# 4__SIM.net
KiCad netlist of a schematic drawn in Altium Designer
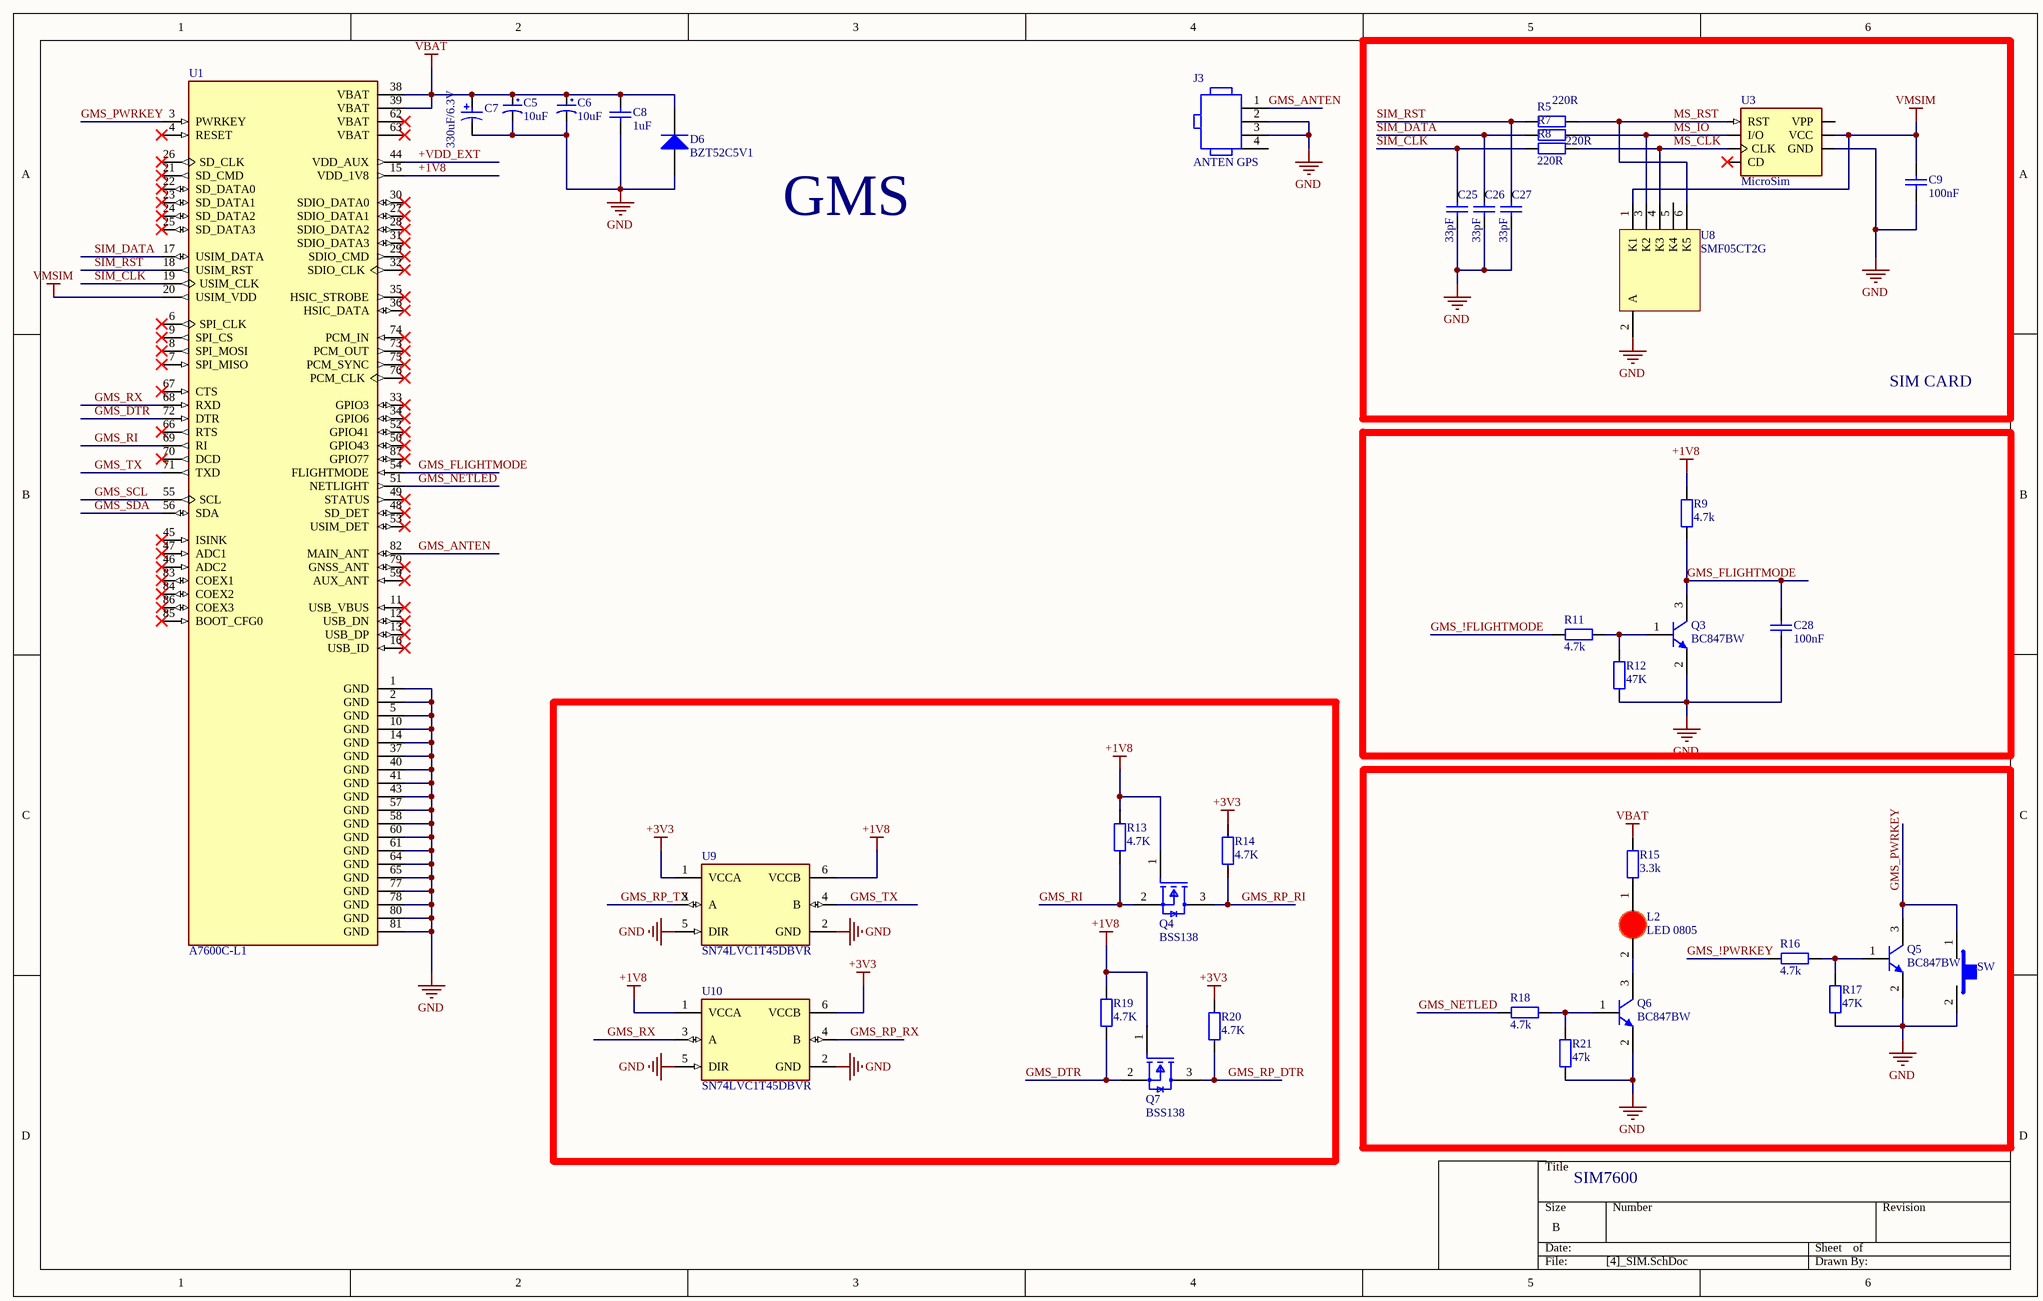
[diagram p0: [4]_SIM.SchDoc]

(export (version "E")
  (design (tool "Eeschema 10.0.6"))
  (components
    (comp (ref "C5")
      (value "10uF")
      (footprint "tu tantalum smd3528")
      (description "Dán")
      (libsource (lib "Altium_Lib_by_KhueNguyenCreator") (part "Tu tantalum 10uF 16V SMD3528"))
    )
    (comp (ref "C6")
      (value "10uF")
      (footprint "tu tantalum smd3528")
      (description "Dán")
      (libsource (lib "Altium_Lib_by_KhueNguyenCreator") (part "Tu tantalum 10uF 16V SMD3528"))
    )
    (comp (ref "C7")
      (value "330uF/6.3V")
      (footprint "NIC-CAPA2-6.3X7.7_V")
      (fields (field (name "PARTNUMBER") "UUD0J331MCL1GS") (field (name "MANUFACTURER") "Nichicon"))
      (libsource (lib "Altium Content Vault") (part "NIC-CAP-P-2"))
    )
    (comp (ref "C8")
      (value "1uF")
      (footprint "tu 0603")
      (description "Dán")
      (libsource (lib "Altium_Lib_by_KhueNguyenCreator") (part "Tu 0603 104 50V 10%"))
    )
    (comp (ref "C9")
      (value "100nF")
      (footprint "tu 0603")
      (description "Dán")
      (libsource (lib "Altium_Lib_by_KhueNguyenCreator") (part "Tu 0603 105 16V 20%"))
    )
    (comp (ref "C25")
      (value "33pF")
      (footprint "tu 0603")
      (description "Dán")
      (libsource (lib "Altium_Lib_by_KhueNguyenCreator") (part "Tu 0603 104 50V 10%"))
    )
    (comp (ref "C26")
      (value "33pF")
      (footprint "tu 0603")
      (description "Dán")
      (libsource (lib "Altium_Lib_by_KhueNguyenCreator") (part "Tu 0603 104 50V 10%"))
    )
    (comp (ref "C27")
      (value "33pF")
      (footprint "tu 0603")
      (description "Dán")
      (libsource (lib "Altium_Lib_by_KhueNguyenCreator") (part "Tu 0603 104 50V 10%"))
    )
    (comp (ref "C28")
      (value "100nF")
      (footprint "tu 0603")
      (description "Dán")
      (libsource (lib "Altium_Lib_by_KhueNguyenCreator") (part "Tu 0603 105 16V 20%"))
    )
    (comp (ref "D6")
      (value "BZT52C5V1")
      (footprint "DIODE SOD-123")
      (description "Dán")
      (libsource (lib "Altium_Lib_by_KhueNguyenCreator") (part "Diode S4"))
    )
    (comp (ref "J3")
      (value "ANTEN GPS")
      (footprint "TG-RECE-20369-001E-4_V")
      (description "RF Connector, Onboard Receptacle, IPEX MHFIII")
      (fields (field (name "MANUFACTURER") "Taoglas") (field (name "PARTNUMBER") "RECE-20369-001E-01"))
      (libsource (lib "Altium Content Vault") (part "TG-RECE-20369-001E-01-4"))
    )
    (comp (ref "L2")
      (value "LED 0805")
      (footprint "LED-0805-Red")
      (description "Dán")
      (libsource (lib "Altium_Lib_by_KhueNguyenCreator") (part "LED 0805 Do"))
    )
    (comp (ref "Q3")
      (value "BC847BW")
      (footprint "INF-SOT323_N")
      (description "NPN Silicon AF Transistor, 45 V VCEO, 100 mA IC, SOT323, Reel, Green")
      (fields (field (name "MANUFACTURER") "Infineon"))
      (libsource (lib "Altium Content Vault") (part "INF-BJTNPN-BEC-3"))
    )
    (comp (ref "Q4")
      (value "BSS138")
      (footprint "FP-SOT23-IPC_C")
      (description "MOSFET N-CH 50V 500MA SOT23")
      (libsource (lib "Altium Content Vault") (part "0a9ea7c96deaaede766a5b531c28de0"))
    )
    (comp (ref "Q5")
      (value "BC847BW")
      (footprint "INF-SOT323_N")
      (description "NPN Silicon AF Transistor, 45 V VCEO, 100 mA IC, SOT323, Reel, Green")
      (fields (field (name "MANUFACTURER") "Infineon"))
      (libsource (lib "Altium Content Vault") (part "INF-BJTNPN-BEC-3"))
    )
    (comp (ref "Q6")
      (value "BC847BW")
      (footprint "INF-SOT323_N")
      (description "NPN Silicon AF Transistor, 45 V VCEO, 100 mA IC, SOT323, Reel, Green")
      (fields (field (name "MANUFACTURER") "Infineon"))
      (libsource (lib "Altium Content Vault") (part "INF-BJTNPN-BEC-3"))
    )
    (comp (ref "Q7")
      (value "BSS138")
      (footprint "FP-SOT23-IPC_C")
      (description "MOSFET N-CH 50V 500MA SOT23")
      (libsource (lib "Altium Content Vault") (part "0a9ea7c96deaaede766a5b531c28de0"))
    )
    (comp (ref "R5")
      (value "220R")
      (footprint "tro smd 0603")
      (description "Dán")
      (libsource (lib "Altium_Lib_by_KhueNguyenCreator") (part "Tro 0603 5% 220R"))
    )
    (comp (ref "R7")
      (value "220R")
      (footprint "tro smd 0603")
      (description "Dán")
      (libsource (lib "Altium_Lib_by_KhueNguyenCreator") (part "Tro 0603 5% 220R"))
    )
    (comp (ref "R8")
      (value "220R")
      (footprint "tro smd 0603")
      (description "Dán")
      (libsource (lib "Altium_Lib_by_KhueNguyenCreator") (part "Tro 0603 5% 220R"))
    )
    (comp (ref "R9")
      (value "4.7k")
      (footprint "tro smd 0603")
      (description "Dán")
      (libsource (lib "Altium_Lib_by_KhueNguyenCreator") (part "Tro 0603 5% 1k"))
    )
    (comp (ref "R11")
      (value "4.7k")
      (footprint "tro smd 0603")
      (description "Dán")
      (libsource (lib "Altium_Lib_by_KhueNguyenCreator") (part "Tro 0603 5% 1k"))
    )
    (comp (ref "R12")
      (value "47K")
      (footprint "tro smd 0603")
      (description "Dán")
      (libsource (lib "Altium_Lib_by_KhueNguyenCreator") (part "Tro 0603 5% 100k"))
    )
    (comp (ref "R13")
      (value "4.7K")
      (footprint "tro smd 0603")
      (description "Dán")
      (libsource (lib "Altium_Lib_by_KhueNguyenCreator") (part "Tro 0603 5% 1k"))
    )
    (comp (ref "R14")
      (value "4.7K")
      (footprint "tro smd 0603")
      (description "Dán")
      (libsource (lib "Altium_Lib_by_KhueNguyenCreator") (part "Tro 0603 5% 1k"))
    )
    (comp (ref "R15")
      (value "3.3k")
      (footprint "tro smd 0603")
      (description "Dán")
      (libsource (lib "Altium_Lib_by_KhueNguyenCreator") (part "Tro 0603 5% 1k"))
    )
    (comp (ref "R16")
      (value "4.7k")
      (footprint "tro smd 0603")
      (description "Dán")
      (libsource (lib "Altium_Lib_by_KhueNguyenCreator") (part "Tro 0603 5% 1k"))
    )
    (comp (ref "R17")
      (value "47K")
      (footprint "tro smd 0603")
      (description "Dán")
      (libsource (lib "Altium_Lib_by_KhueNguyenCreator") (part "Tro 0603 5% 100k"))
    )
    (comp (ref "R18")
      (value "4.7k")
      (footprint "tro smd 0603")
      (description "Dán")
      (libsource (lib "Altium_Lib_by_KhueNguyenCreator") (part "Tro 0603 5% 1k"))
    )
    (comp (ref "R19")
      (value "4.7K")
      (footprint "tro smd 0603")
      (description "Dán")
      (libsource (lib "Altium_Lib_by_KhueNguyenCreator") (part "Tro 0603 5% 1k"))
    )
    (comp (ref "R20")
      (value "4.7K")
      (footprint "tro smd 0603")
      (description "Dán")
      (libsource (lib "Altium_Lib_by_KhueNguyenCreator") (part "Tro 0603 5% 1k"))
    )
    (comp (ref "R21")
      (value "47k")
      (footprint "tro smd 0603")
      (description "Dán")
      (libsource (lib "Altium_Lib_by_KhueNguyenCreator") (part "Tro 0603 5% 100k"))
    )
    (comp (ref "SW")
      (value "Tactile")
      (footprint "SW 2P SMD")
      (description "SMD Mini Push Button Switch 2 Pin 3x6x2.7mm")
      (fields (field (name "MANUFACTURER") "OEM") (field (name "PART NUMBER") "SPST 2 PIN SMD"))
      (libsource (lib "COMPONENT_INS") (part "SW_SPDT_2PIN"))
    )
    (comp (ref "U1")
      (value "A7600C-L1")
      (footprint "SIMA7600C")
      (libsource (lib "COMPONENT_INS") (part "SIMA7600C"))
    )
    (comp (ref "U3")
      (value "MicroSim")
      (footprint "Micro-Sim-7P")
      (description "MS-PP-7P Khay Cắm Micro Sim 7 Chân Push-Push")
      (fields (field (name "MANUFACTURER") "Samsung") (field (name "PART NUMBER") "C0805"))
      (libsource (lib "COMPONENT_INS") (part "Micro_Sim_7Pin"))
    )
    (comp (ref "U8")
      (value "SMF05CT2G")
      (footprint "ONSC-SC70-6-419B-02_W_V")
      (description "5-Line Transient Voltage Suppressor Array, 6-Pin SC70, Pb-Free, Tape and Reel")
      (fields (field (name "MANUFACTURER") "On Semiconductor"))
      (libsource (lib "Altium Content Vault") (part "ONSC-K1A2K3K4K5K6-6"))
    )
    (comp (ref "U9")
      (value "SN74LVC1T45DBVR")
      (footprint "FP-DBV0006A-IPC_B")
      (description "IC TRNSLTR BIDIRECTIONAL SOT23-6")
      (libsource (lib "Altium Content Vault") (part "7317ea058f373ab919a7c78c581a60e"))
    )
    (comp (ref "U10")
      (value "SN74LVC1T45DBVR")
      (footprint "FP-DBV0006A-IPC_B")
      (description "IC TRNSLTR BIDIRECTIONAL SOT23-6")
      (libsource (lib "Altium Content Vault") (part "7317ea058f373ab919a7c78c581a60e"))
    )
  )
  (nets
    (net (code "1") (name "+1V8") (class "Default")
      (node (ref "Q4") (pin "1") (pinfunction "G_1") (pintype "passive"))
      (node (ref "Q7") (pin "1") (pinfunction "G_1") (pintype "passive"))
      (node (ref "R13") (pin "1") (pinfunction "1_1") (pintype "passive"))
      (node (ref "R19") (pin "1") (pinfunction "1_1") (pintype "passive"))
      (node (ref "R9") (pin "2") (pinfunction "2_2") (pintype "passive"))
      (node (ref "U1") (pin "15") (pinfunction "VDD_1V8_15") (pintype "output"))
      (node (ref "U10") (pin "1") (pinfunction "VCCA_1") (pintype "power_in"))
      (node (ref "U9") (pin "6") (pinfunction "VCCB_6") (pintype "power_in"))
    )
    (net (code "2") (name "+3V3") (class "Default")
      (node (ref "R14") (pin "2") (pinfunction "2_2") (pintype "passive"))
      (node (ref "R20") (pin "2") (pinfunction "2_2") (pintype "passive"))
      (node (ref "U10") (pin "6") (pinfunction "VCCB_6") (pintype "power_in"))
      (node (ref "U9") (pin "1") (pinfunction "VCCA_1") (pintype "power_in"))
    )
    (net (code "3") (name "/+VDD_EXT") (class "Default")
      (node (ref "U1") (pin "44") (pinfunction "VDD_AUX_44") (pintype "output"))
    )
    (net (code "5") (name "/GMS_!FLIGHTMODE") (class "Default")
      (node (ref "R11") (pin "1") (pinfunction "1_1") (pintype "passive"))
    )
    (net (code "6") (name "/GMS_!PWRKEY") (class "Default")
      (node (ref "R16") (pin "1") (pinfunction "1_1") (pintype "passive"))
    )
    (net (code "7") (name "/GMS_ANTEN") (class "Default")
      (node (ref "J3") (pin "1") (pinfunction "1_1") (pintype "passive"))
      (node (ref "U1") (pin "82") (pinfunction "MAIN_ANT_82") (pintype "bidirectional"))
    )
    (net (code "8") (name "/GMS_DTR") (class "Default")
      (node (ref "Q7") (pin "2") (pinfunction "S_2") (pintype "passive"))
      (node (ref "R19") (pin "2") (pinfunction "2_2") (pintype "passive"))
      (node (ref "U1") (pin "72") (pinfunction "DTR_72") (pintype "input"))
    )
    (net (code "9") (name "/GMS_FLIGHTMODE") (class "Default")
      (node (ref "C28") (pin "1") (pinfunction "1_1") (pintype "passive"))
      (node (ref "Q3") (pin "3") (pinfunction "C_3") (pintype "passive"))
      (node (ref "R9") (pin "1") (pinfunction "1_1") (pintype "passive"))
      (node (ref "U1") (pin "54") (pinfunction "FLIGHTMODE_54") (pintype "input"))
    )
    (net (code "10") (name "/GMS_NETLED") (class "Default")
      (node (ref "R18") (pin "1") (pinfunction "1_1") (pintype "passive"))
      (node (ref "U1") (pin "51") (pinfunction "NETLIGHT_51") (pintype "output"))
    )
    (net (code "11") (name "/GMS_PWRKEY") (class "Default")
      (node (ref "Q5") (pin "3") (pinfunction "C_3") (pintype "passive"))
      (node (ref "SW") (pin "1") (pinfunction "1_1") (pintype "passive"))
      (node (ref "U1") (pin "3") (pinfunction "PWRKEY_3") (pintype "input"))
    )
    (net (code "12") (name "/GMS_RI") (class "Default")
      (node (ref "Q4") (pin "2") (pinfunction "S_2") (pintype "passive"))
      (node (ref "R13") (pin "2") (pinfunction "2_2") (pintype "passive"))
      (node (ref "U1") (pin "69") (pinfunction "RI_69") (pintype "output"))
    )
    (net (code "13") (name "/GMS_RP_DTR") (class "Default")
      (node (ref "Q7") (pin "3") (pinfunction "D_3") (pintype "passive"))
      (node (ref "R20") (pin "1") (pinfunction "1_1") (pintype "passive"))
    )
    (net (code "14") (name "/GMS_RP_RI") (class "Default")
      (node (ref "Q4") (pin "3") (pinfunction "D_3") (pintype "passive"))
      (node (ref "R14") (pin "1") (pinfunction "1_1") (pintype "passive"))
    )
    (net (code "15") (name "/GMS_RP_RX") (class "Default")
      (node (ref "U10") (pin "4") (pinfunction "B_4") (pintype "bidirectional"))
    )
    (net (code "16") (name "/GMS_RP_TX") (class "Default")
      (node (ref "U9") (pin "3") (pinfunction "A_3") (pintype "bidirectional"))
    )
    (net (code "17") (name "/GMS_RX") (class "Default")
      (node (ref "U1") (pin "68") (pinfunction "RXD_68") (pintype "input"))
      (node (ref "U10") (pin "3") (pinfunction "A_3") (pintype "bidirectional"))
    )
    (net (code "18") (name "/GMS_SCL") (class "Default")
      (node (ref "U1") (pin "55") (pinfunction "SCL_55") (pintype "output"))
    )
    (net (code "19") (name "/GMS_SDA") (class "Default")
      (node (ref "U1") (pin "56") (pinfunction "SDA_56") (pintype "bidirectional"))
    )
    (net (code "20") (name "/GMS_TX") (class "Default")
      (node (ref "U1") (pin "71") (pinfunction "TXD_71") (pintype "output"))
      (node (ref "U9") (pin "4") (pinfunction "B_4") (pintype "bidirectional"))
    )
    (net (code "21") (name "/MS_CLK") (class "Default")
      (node (ref "R8") (pin "2") (pinfunction "2_2") (pintype "passive"))
      (node (ref "U3") (pin "C3") (pinfunction "CLK_C3") (pintype "bidirectional"))
      (node (ref "U8") (pin "4") (pinfunction "K3_4") (pintype "passive"))
    )
    (net (code "22") (name "/MS_IO") (class "Default")
      (node (ref "R7") (pin "2") (pinfunction "2_2") (pintype "passive"))
      (node (ref "U3") (pin "C7") (pinfunction "I/O_C7") (pintype "bidirectional"))
      (node (ref "U8") (pin "3") (pinfunction "K2_3") (pintype "passive"))
    )
    (net (code "23") (name "/MS_RST") (class "Default")
      (node (ref "R5") (pin "2") (pinfunction "2_2") (pintype "passive"))
      (node (ref "U3") (pin "C2") (pinfunction "RST_C2") (pintype "input"))
      (node (ref "U8") (pin "6") (pinfunction "K5_6") (pintype "passive"))
    )
    (net (code "24") (name "/SIM_CLK") (class "Default")
      (node (ref "C25") (pin "1") (pinfunction "1_1") (pintype "passive"))
      (node (ref "R8") (pin "1") (pinfunction "1_1") (pintype "passive"))
      (node (ref "U1") (pin "19") (pinfunction "USIM_CLK_19") (pintype "output"))
    )
    (net (code "25") (name "/SIM_DATA") (class "Default")
      (node (ref "C26") (pin "1") (pinfunction "1_1") (pintype "passive"))
      (node (ref "R7") (pin "1") (pinfunction "1_1") (pintype "passive"))
      (node (ref "U1") (pin "17") (pinfunction "USIM_DATA_17") (pintype "bidirectional"))
    )
    (net (code "26") (name "/SIM_RST") (class "Default")
      (node (ref "C27") (pin "1") (pinfunction "1_1") (pintype "passive"))
      (node (ref "R5") (pin "1") (pinfunction "1_1") (pintype "passive"))
      (node (ref "U1") (pin "18") (pinfunction "USIM_RST_18") (pintype "output"))
    )
    (net (code "27") (name "GND") (class "Default")
      (node (ref "C25") (pin "2") (pinfunction "2_2") (pintype "passive"))
      (node (ref "C26") (pin "2") (pinfunction "2_2") (pintype "passive"))
      (node (ref "C27") (pin "2") (pinfunction "2_2") (pintype "passive"))
      (node (ref "C28") (pin "2") (pinfunction "2_2") (pintype "passive"))
      (node (ref "C5") (pin "2") (pinfunction "2_2") (pintype "passive"))
      (node (ref "C6") (pin "2") (pinfunction "2_2") (pintype "passive"))
      (node (ref "C7") (pin "2") (pinfunction "2_2") (pintype "passive"))
      (node (ref "C8") (pin "2") (pinfunction "2_2") (pintype "passive"))
      (node (ref "C9") (pin "2") (pinfunction "2_2") (pintype "passive"))
      (node (ref "D6") (pin "1") (pinfunction "A_1") (pintype "passive"))
      (node (ref "J3") (pin "2") (pinfunction "2_2") (pintype "passive"))
      (node (ref "J3") (pin "3") (pinfunction "3_3") (pintype "passive"))
      (node (ref "Q3") (pin "2") (pinfunction "E_2") (pintype "passive"))
      (node (ref "Q5") (pin "2") (pinfunction "E_2") (pintype "passive"))
      (node (ref "Q6") (pin "2") (pinfunction "E_2") (pintype "passive"))
      (node (ref "R12") (pin "1") (pinfunction "1_1") (pintype "passive"))
      (node (ref "R17") (pin "1") (pinfunction "1_1") (pintype "passive"))
      (node (ref "R21") (pin "1") (pinfunction "1_1") (pintype "passive"))
      (node (ref "SW") (pin "2") (pinfunction "2_2") (pintype "passive"))
      (node (ref "U1") (pin "1") (pinfunction "GND_1") (pintype "power_in"))
      (node (ref "U1") (pin "10") (pinfunction "GND_10") (pintype "power_in"))
      (node (ref "U1") (pin "14") (pinfunction "GND_14") (pintype "power_in"))
      (node (ref "U1") (pin "2") (pinfunction "GND_2") (pintype "power_in"))
      (node (ref "U1") (pin "37") (pinfunction "GND_37") (pintype "power_in"))
      (node (ref "U1") (pin "40") (pinfunction "GND_40") (pintype "power_in"))
      (node (ref "U1") (pin "41") (pinfunction "GND_41") (pintype "power_in"))
      (node (ref "U1") (pin "43") (pinfunction "GND_43") (pintype "power_in"))
      (node (ref "U1") (pin "5") (pinfunction "GND_5") (pintype "power_in"))
      (node (ref "U1") (pin "57") (pinfunction "GND_57") (pintype "power_in"))
      (node (ref "U1") (pin "58") (pinfunction "GND_58") (pintype "power_in"))
      (node (ref "U1") (pin "60") (pinfunction "GND_60") (pintype "power_in"))
      (node (ref "U1") (pin "61") (pinfunction "GND_61") (pintype "power_in"))
      (node (ref "U1") (pin "64") (pinfunction "GND_64") (pintype "power_in"))
      (node (ref "U1") (pin "65") (pinfunction "GND_65") (pintype "power_in"))
      (node (ref "U1") (pin "77") (pinfunction "GND_77") (pintype "power_in"))
      (node (ref "U1") (pin "78") (pinfunction "GND_78") (pintype "power_in"))
      (node (ref "U1") (pin "80") (pinfunction "GND_80") (pintype "power_in"))
      (node (ref "U1") (pin "81") (pinfunction "GND_81") (pintype "power_in"))
      (node (ref "U10") (pin "2") (pinfunction "GND_2") (pintype "power_in"))
      (node (ref "U10") (pin "5") (pinfunction "DIR_5") (pintype "input"))
      (node (ref "U3") (pin "C5") (pinfunction "GND_C5") (pintype "power_in"))
      (node (ref "U8") (pin "2") (pinfunction "A_2") (pintype "passive"))
      (node (ref "U9") (pin "2") (pinfunction "GND_2") (pintype "power_in"))
      (node (ref "U9") (pin "5") (pinfunction "DIR_5") (pintype "input"))
    )
    (net (code "28") (name "Net-(L2-A)") (class "Default")
      (node (ref "L2") (pin "1") (pinfunction "A_1") (pintype "passive"))
      (node (ref "R15") (pin "1") (pinfunction "1_1") (pintype "passive"))
    )
    (net (code "29") (name "Net-(L2-K)") (class "Default")
      (node (ref "L2") (pin "2") (pinfunction "K_2") (pintype "passive"))
      (node (ref "Q6") (pin "3") (pinfunction "C_3") (pintype "passive"))
    )
    (net (code "30") (name "Net-(Q3-B)") (class "Default")
      (node (ref "Q3") (pin "1") (pinfunction "B_1") (pintype "passive"))
      (node (ref "R11") (pin "2") (pinfunction "2_2") (pintype "passive"))
      (node (ref "R12") (pin "2") (pinfunction "2_2") (pintype "passive"))
    )
    (net (code "31") (name "Net-(Q5-B)") (class "Default")
      (node (ref "Q5") (pin "1") (pinfunction "B_1") (pintype "passive"))
      (node (ref "R16") (pin "2") (pinfunction "2_2") (pintype "passive"))
      (node (ref "R17") (pin "2") (pinfunction "2_2") (pintype "passive"))
    )
    (net (code "32") (name "Net-(Q6-B)") (class "Default")
      (node (ref "Q6") (pin "1") (pinfunction "B_1") (pintype "passive"))
      (node (ref "R18") (pin "2") (pinfunction "2_2") (pintype "passive"))
      (node (ref "R21") (pin "2") (pinfunction "2_2") (pintype "passive"))
    )
    (net (code "33") (name "VBAT") (class "Default")
      (node (ref "C5") (pin "1") (pinfunction "1_1") (pintype "passive"))
      (node (ref "C6") (pin "1") (pinfunction "1_1") (pintype "passive"))
      (node (ref "C7") (pin "1") (pinfunction "1_1") (pintype "passive"))
      (node (ref "C8") (pin "1") (pinfunction "1_1") (pintype "passive"))
      (node (ref "D6") (pin "2") (pinfunction "K_2") (pintype "passive"))
      (node (ref "R15") (pin "2") (pinfunction "2_2") (pintype "passive"))
      (node (ref "U1") (pin "38") (pinfunction "VBAT_38") (pintype "power_in"))
      (node (ref "U1") (pin "39") (pinfunction "VBAT_39") (pintype "power_in"))
    )
    (net (code "34") (name "VMSIM") (class "Default")
      (node (ref "C9") (pin "1") (pinfunction "1_1") (pintype "passive"))
      (node (ref "U1") (pin "20") (pinfunction "USIM_VDD_20") (pintype "output"))
      (node (ref "U3") (pin "C1") (pinfunction "VCC_C1") (pintype "power_in"))
      (node (ref "U8") (pin "1") (pinfunction "K1_1") (pintype "passive"))
    )
    (net (code "35") (name "unconnected-(J3-Pad4)") (class "Default")
      (node (ref "J3") (pin "4") (pinfunction "4_4") (pintype "passive"))
    )
    (net (code "36") (name "unconnected-(U1-ADC1-Pad47)") (class "Default")
      (node (ref "U1") (pin "47") (pinfunction "ADC1_47") (pintype "input+no_connect"))
    )
    (net (code "37") (name "unconnected-(U1-ADC2-Pad46)") (class "Default")
      (node (ref "U1") (pin "46") (pinfunction "ADC2_46") (pintype "input+no_connect"))
    )
    (net (code "38") (name "unconnected-(U1-AUX_ANT-Pad59)") (class "Default")
      (node (ref "U1") (pin "59") (pinfunction "AUX_ANT_59") (pintype "input+no_connect"))
    )
    (net (code "39") (name "unconnected-(U1-BOOT_CFG0-Pad85)") (class "Default")
      (node (ref "U1") (pin "85") (pinfunction "BOOT_CFG0_85") (pintype "input+no_connect"))
    )
    (net (code "40") (name "unconnected-(U1-COEX1-Pad83)") (class "Default")
      (node (ref "U1") (pin "83") (pinfunction "COEX1_83") (pintype "bidirectional+no_connect"))
    )
    (net (code "41") (name "unconnected-(U1-COEX2-Pad84)") (class "Default")
      (node (ref "U1") (pin "84") (pinfunction "COEX2_84") (pintype "bidirectional+no_connect"))
    )
    (net (code "42") (name "unconnected-(U1-COEX3-Pad86)") (class "Default")
      (node (ref "U1") (pin "86") (pinfunction "COEX3_86") (pintype "bidirectional+no_connect"))
    )
    (net (code "43") (name "unconnected-(U1-CTS-Pad67)") (class "Default")
      (node (ref "U1") (pin "67") (pinfunction "CTS_67") (pintype "input+no_connect"))
    )
    (net (code "44") (name "unconnected-(U1-DCD-Pad70)") (class "Default")
      (node (ref "U1") (pin "70") (pinfunction "DCD_70") (pintype "output+no_connect"))
    )
    (net (code "45") (name "unconnected-(U1-GNSS_ANT-Pad79)") (class "Default")
      (node (ref "U1") (pin "79") (pinfunction "GNSS_ANT_79") (pintype "bidirectional+no_connect"))
    )
    (net (code "46") (name "unconnected-(U1-GPIO3-Pad33)") (class "Default")
      (node (ref "U1") (pin "33") (pinfunction "GPIO3_33") (pintype "bidirectional+no_connect"))
    )
    (net (code "47") (name "unconnected-(U1-GPIO6-Pad34)") (class "Default")
      (node (ref "U1") (pin "34") (pinfunction "GPIO6_34") (pintype "bidirectional+no_connect"))
    )
    (net (code "48") (name "unconnected-(U1-GPIO41-Pad52)") (class "Default")
      (node (ref "U1") (pin "52") (pinfunction "GPIO41_52") (pintype "bidirectional+no_connect"))
    )
    (net (code "49") (name "unconnected-(U1-GPIO43-Pad50)") (class "Default")
      (node (ref "U1") (pin "50") (pinfunction "GPIO43_50") (pintype "bidirectional+no_connect"))
    )
    (net (code "50") (name "unconnected-(U1-GPIO77-Pad87)") (class "Default")
      (node (ref "U1") (pin "87") (pinfunction "GPIO77_87") (pintype "bidirectional+no_connect"))
    )
    (net (code "51") (name "unconnected-(U1-HSIC_DATA-Pad36)") (class "Default")
      (node (ref "U1") (pin "36") (pinfunction "HSIC_DATA_36") (pintype "bidirectional+no_connect"))
    )
    (net (code "52") (name "unconnected-(U1-HSIC_STROBE-Pad35)") (class "Default")
      (node (ref "U1") (pin "35") (pinfunction "HSIC_STROBE_35") (pintype "output+no_connect"))
    )
    (net (code "53") (name "unconnected-(U1-ISINK-Pad45)") (class "Default")
      (node (ref "U1") (pin "45") (pinfunction "ISINK_45") (pintype "input+no_connect"))
    )
    (net (code "54") (name "unconnected-(U1-PCM_CLK-Pad76)") (class "Default")
      (node (ref "U1") (pin "76") (pinfunction "PCM_CLK_76") (pintype "output+no_connect"))
    )
    (net (code "55") (name "unconnected-(U1-PCM_IN-Pad74)") (class "Default")
      (node (ref "U1") (pin "74") (pinfunction "PCM_IN_74") (pintype "input+no_connect"))
    )
    (net (code "56") (name "unconnected-(U1-PCM_OUT-Pad73)") (class "Default")
      (node (ref "U1") (pin "73") (pinfunction "PCM_OUT_73") (pintype "output+no_connect"))
    )
    (net (code "57") (name "unconnected-(U1-PCM_SYNC-Pad75)") (class "Default")
      (node (ref "U1") (pin "75") (pinfunction "PCM_SYNC_75") (pintype "output+no_connect"))
    )
    (net (code "58") (name "unconnected-(U1-RESET-Pad4)") (class "Default")
      (node (ref "U1") (pin "4") (pinfunction "RESET_4") (pintype "input+no_connect"))
    )
    (net (code "59") (name "unconnected-(U1-RTS-Pad66)") (class "Default")
      (node (ref "U1") (pin "66") (pinfunction "RTS_66") (pintype "output+no_connect"))
    )
    (net (code "60") (name "unconnected-(U1-SDIO_CLK-Pad32)") (class "Default")
      (node (ref "U1") (pin "32") (pinfunction "SDIO_CLK_32") (pintype "output+no_connect"))
    )
    (net (code "61") (name "unconnected-(U1-SDIO_CMD-Pad29)") (class "Default")
      (node (ref "U1") (pin "29") (pinfunction "SDIO_CMD_29") (pintype "output+no_connect"))
    )
    (net (code "62") (name "unconnected-(U1-SDIO_DATA0-Pad30)") (class "Default")
      (node (ref "U1") (pin "30") (pinfunction "SDIO_DATA0_30") (pintype "bidirectional+no_connect"))
    )
    (net (code "63") (name "unconnected-(U1-SDIO_DATA1-Pad27)") (class "Default")
      (node (ref "U1") (pin "27") (pinfunction "SDIO_DATA1_27") (pintype "bidirectional+no_connect"))
    )
    (net (code "64") (name "unconnected-(U1-SDIO_DATA2-Pad28)") (class "Default")
      (node (ref "U1") (pin "28") (pinfunction "SDIO_DATA2_28") (pintype "bidirectional+no_connect"))
    )
    (net (code "65") (name "unconnected-(U1-SDIO_DATA3-Pad31)") (class "Default")
      (node (ref "U1") (pin "31") (pinfunction "SDIO_DATA3_31") (pintype "bidirectional+no_connect"))
    )
    (net (code "66") (name "unconnected-(U1-SD_CLK-Pad26)") (class "Default")
      (node (ref "U1") (pin "26") (pinfunction "SD_CLK_26") (pintype "output+no_connect"))
    )
    (net (code "67") (name "unconnected-(U1-SD_CMD-Pad21)") (class "Default")
      (node (ref "U1") (pin "21") (pinfunction "SD_CMD_21") (pintype "output+no_connect"))
    )
    (net (code "68") (name "unconnected-(U1-SD_DATA0-Pad22)") (class "Default")
      (node (ref "U1") (pin "22") (pinfunction "SD_DATA0_22") (pintype "bidirectional+no_connect"))
    )
    (net (code "69") (name "unconnected-(U1-SD_DATA1-Pad23)") (class "Default")
      (node (ref "U1") (pin "23") (pinfunction "SD_DATA1_23") (pintype "bidirectional+no_connect"))
    )
    (net (code "70") (name "unconnected-(U1-SD_DATA2-Pad24)") (class "Default")
      (node (ref "U1") (pin "24") (pinfunction "SD_DATA2_24") (pintype "bidirectional+no_connect"))
    )
    (net (code "71") (name "unconnected-(U1-SD_DATA3-Pad25)") (class "Default")
      (node (ref "U1") (pin "25") (pinfunction "SD_DATA3_25") (pintype "bidirectional+no_connect"))
    )
    (net (code "72") (name "unconnected-(U1-SD_DET-Pad48)") (class "Default")
      (node (ref "U1") (pin "48") (pinfunction "SD_DET_48") (pintype "bidirectional+no_connect"))
    )
    (net (code "73") (name "unconnected-(U1-SPI_CLK-Pad6)") (class "Default")
      (node (ref "U1") (pin "6") (pinfunction "SPI_CLK_6") (pintype "output+no_connect"))
    )
    (net (code "74") (name "unconnected-(U1-SPI_CS-Pad9)") (class "Default")
      (node (ref "U1") (pin "9") (pinfunction "SPI_CS_9") (pintype "output+no_connect"))
    )
    (net (code "75") (name "unconnected-(U1-SPI_MISO-Pad7)") (class "Default")
      (node (ref "U1") (pin "7") (pinfunction "SPI_MISO_7") (pintype "input+no_connect"))
    )
    (net (code "76") (name "unconnected-(U1-SPI_MOSI-Pad8)") (class "Default")
      (node (ref "U1") (pin "8") (pinfunction "SPI_MOSI_8") (pintype "output+no_connect"))
    )
    (net (code "77") (name "unconnected-(U1-STATUS-Pad49)") (class "Default")
      (node (ref "U1") (pin "49") (pinfunction "STATUS_49") (pintype "output+no_connect"))
    )
    (net (code "78") (name "unconnected-(U1-USB_DN-Pad12)") (class "Default")
      (node (ref "U1") (pin "12") (pinfunction "USB_DN_12") (pintype "bidirectional+no_connect"))
    )
    (net (code "79") (name "unconnected-(U1-USB_DP-Pad13)") (class "Default")
      (node (ref "U1") (pin "13") (pinfunction "USB_DP_13") (pintype "bidirectional+no_connect"))
    )
    (net (code "80") (name "unconnected-(U1-USB_ID-Pad16)") (class "Default")
      (node (ref "U1") (pin "16") (pinfunction "USB_ID_16") (pintype "input+no_connect"))
    )
    (net (code "81") (name "unconnected-(U1-USB_VBUS-Pad11)") (class "Default")
      (node (ref "U1") (pin "11") (pinfunction "USB_VBUS_11") (pintype "input+no_connect"))
    )
    (net (code "82") (name "unconnected-(U1-USIM_DET-Pad53)") (class "Default")
      (node (ref "U1") (pin "53") (pinfunction "USIM_DET_53") (pintype "bidirectional+no_connect"))
    )
    (net (code "83") (name "unconnected-(U1-VBAT-Pad62)") (class "Default")
      (node (ref "U1") (pin "62") (pinfunction "VBAT_62") (pintype "power_in+no_connect"))
    )
    (net (code "84") (name "unconnected-(U1-VBAT-Pad63)") (class "Default")
      (node (ref "U1") (pin "63") (pinfunction "VBAT_63") (pintype "power_in+no_connect"))
    )
    (net (code "85") (name "unconnected-(U3-PadCD)") (class "Default")
      (node (ref "U3") (pin "CD") (pinfunction "CD_CD") (pintype "passive+no_connect"))
    )
    (net (code "86") (name "unconnected-(U3-VPP-PadC6)") (class "Default")
      (node (ref "U3") (pin "C6") (pinfunction "VPP_C6") (pintype "power_in"))
    )
    (net (code "87") (name "unconnected-(U8-K4-Pad5)") (class "Default")
      (node (ref "U8") (pin "5") (pinfunction "K4_5") (pintype "passive"))
    )
  )
)
